# FPGABank3X.net
KiCad netlist of a schematic drawn in Altium Designer
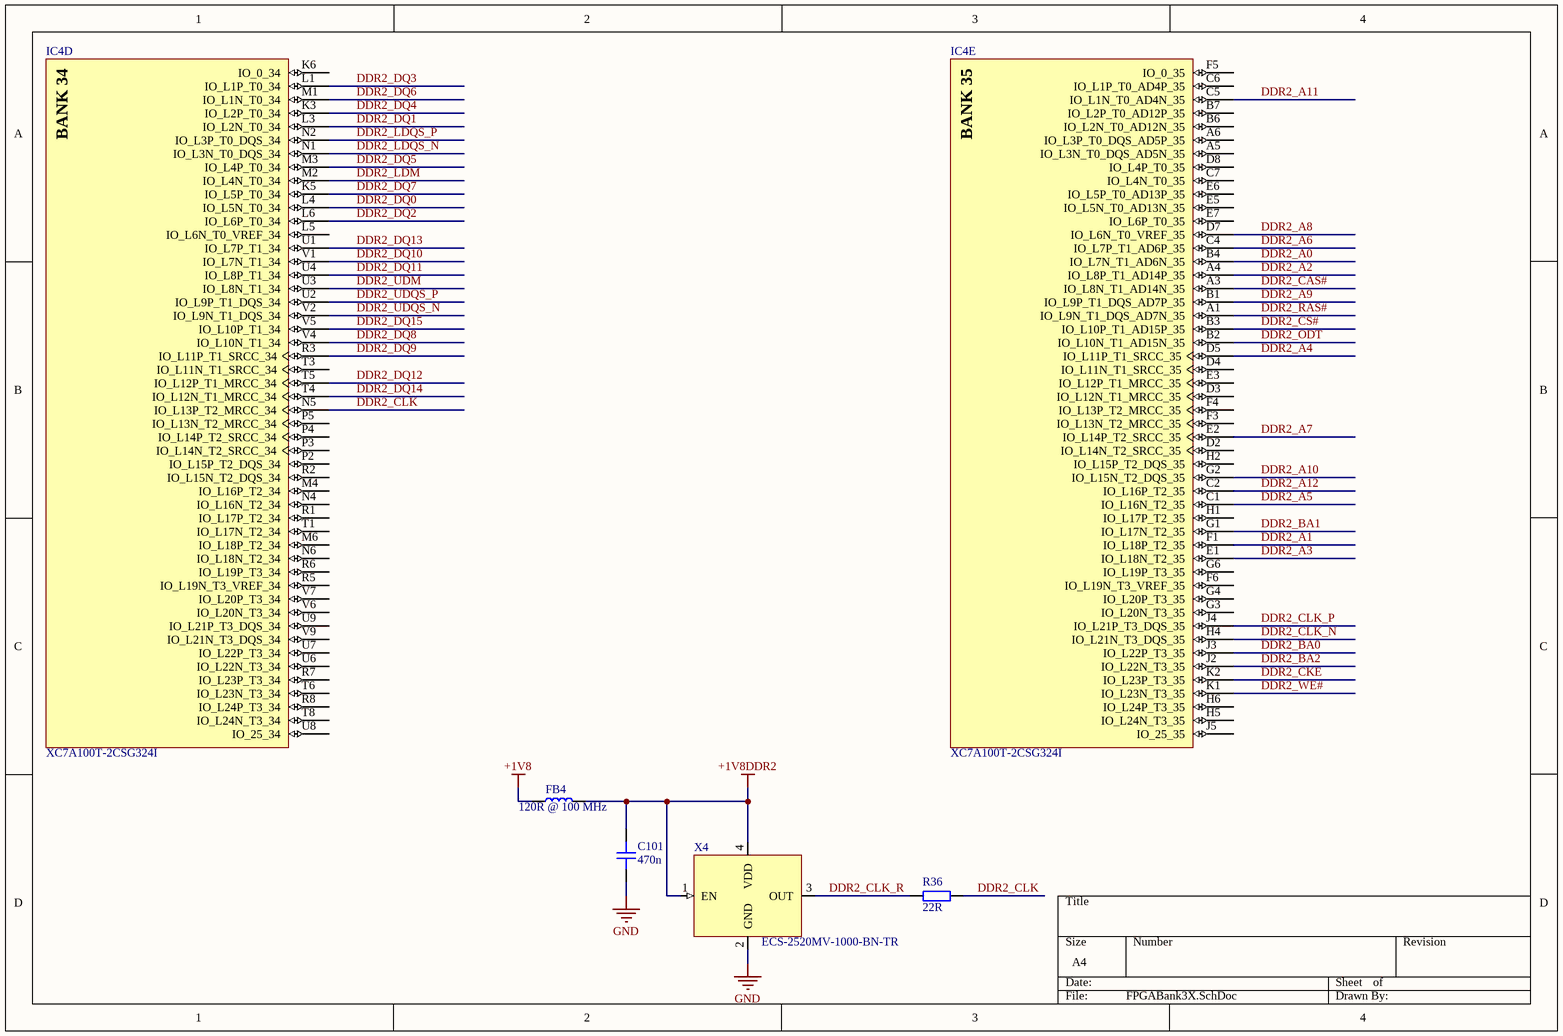
[diagram p0: FPGABank3X.SchDoc]

(export (version "E")
  (design (tool "Eeschema 10.0.6"))
  (components
    (comp (ref "C101")
      (value "470n")
      (footprint "CAP_0201")
      (description "Capacitor SMD 0201")
      (libsource (lib "Schematic-Lib-PhilsLab") (part "CAP_0201"))
    )
    (comp (ref "FB4")
      (value "120R @ 100 MHz")
      (footprint "Footprint-Lib-PhilsLab:IND_0201")
      (description "Inductor SMD 0201")
      (fields
        (field (name "MANUFACTURER_PART_NUMBER") "LQP03HQ56NH02D")
        (field (name "MOUSER PART NUMBER") "81-LQP03HQ56NH02D")
      )
      (libsource (lib "Schematic-Lib-PhilsLab") (part "IND_0201"))
    )
    (comp (ref "IC4")
      (value "XC7A100T-2CSG324I")
      (footprint "CSG324")
      (description "Artix-7 FPGA, 210 User I/Os, 0 GTP, 324-Ball BGA, Speed Grade 2, Industrial Grade, Pb-Free")
      (fields (field (name "GENERIC PART NUMBER") "XC7A100T") (field (name "MANUFACTURER") "Xilinx"))
      (libsource (lib "Schematic-Lib-PhilsLab") (part "XC7A100T-2CSG324I"))
    )
    (comp (ref "R36")
      (value "22R")
      (footprint "RES_0201")
      (description "Resistor SMD 0201")
      (libsource (lib "Schematic-Lib-PhilsLab") (part "RES_0201"))
    )
    (comp (ref "X4")
      (value "ECS-2520MV-1000-BN-TR")
      (footprint "XTAL_2520")
      (fields
        (field (name "MANUFACTURER") "ECS")
        (field (name "MANUFACTURER PART NUMBER") "ECS-2520MV-130-BN-TR")
      )
      (libsource (lib "Schematic-Lib-PhilsLab") (part "ECS-2520MV-130-BN-TR"))
    )
  )
  (nets
    (net (code "1") (name "+1V8") (class "Default")
      (node (ref "FB4") (pin "1") (pinfunction "1_1") (pintype "passive"))
    )
    (net (code "2") (name "+1V8DDR2") (class "Default")
      (node (ref "C101") (pin "2") (pinfunction "2_2") (pintype "passive"))
      (node (ref "FB4") (pin "2") (pinfunction "2_2") (pintype "passive"))
      (node (ref "X4") (pin "1") (pinfunction "EN_1") (pintype "input"))
      (node (ref "X4") (pin "4") (pinfunction "VDD_4") (pintype "power_in"))
    )
    (net (code "3") (name "/DDR2_A0") (class "Default")
      (node (ref "IC4") (pin "B4") (pinfunction "IO_L7N_T1_AD6N_35_B4") (pintype "bidirectional"))
    )
    (net (code "4") (name "/DDR2_A1") (class "Default")
      (node (ref "IC4") (pin "F1") (pinfunction "IO_L18P_T2_35_F1") (pintype "bidirectional"))
    )
    (net (code "5") (name "/DDR2_A2") (class "Default")
      (node (ref "IC4") (pin "A4") (pinfunction "IO_L8P_T1_AD14P_35_A4") (pintype "bidirectional"))
    )
    (net (code "6") (name "/DDR2_A3") (class "Default")
      (node (ref "IC4") (pin "E1") (pinfunction "IO_L18N_T2_35_E1") (pintype "bidirectional"))
    )
    (net (code "7") (name "/DDR2_A4") (class "Default")
      (node (ref "IC4") (pin "D5") (pinfunction "IO_L11P_T1_SRCC_35_D5") (pintype "bidirectional"))
    )
    (net (code "8") (name "/DDR2_A5") (class "Default")
      (node (ref "IC4") (pin "C1") (pinfunction "IO_L16N_T2_35_C1") (pintype "bidirectional"))
    )
    (net (code "9") (name "/DDR2_A6") (class "Default")
      (node (ref "IC4") (pin "C4") (pinfunction "IO_L7P_T1_AD6P_35_C4") (pintype "bidirectional"))
    )
    (net (code "10") (name "/DDR2_A7") (class "Default")
      (node (ref "IC4") (pin "E2") (pinfunction "IO_L14P_T2_SRCC_35_E2") (pintype "bidirectional"))
    )
    (net (code "11") (name "/DDR2_A8") (class "Default")
      (node (ref "IC4") (pin "D7") (pinfunction "IO_L6N_T0_VREF_35_D7") (pintype "bidirectional"))
    )
    (net (code "12") (name "/DDR2_A9") (class "Default")
      (node (ref "IC4") (pin "B1") (pinfunction "IO_L9P_T1_DQS_AD7P_35_B1") (pintype "bidirectional"))
    )
    (net (code "13") (name "/DDR2_A10") (class "Default")
      (node (ref "IC4") (pin "G2") (pinfunction "IO_L15N_T2_DQS_35_G2") (pintype "bidirectional"))
    )
    (net (code "14") (name "/DDR2_A11") (class "Default")
      (node (ref "IC4") (pin "C5") (pinfunction "IO_L1N_T0_AD4N_35_C5") (pintype "bidirectional"))
    )
    (net (code "15") (name "/DDR2_A12") (class "Default")
      (node (ref "IC4") (pin "C2") (pinfunction "IO_L16P_T2_35_C2") (pintype "bidirectional"))
    )
    (net (code "16") (name "/DDR2_BA0") (class "Default")
      (node (ref "IC4") (pin "J3") (pinfunction "IO_L22P_T3_35_J3") (pintype "bidirectional"))
    )
    (net (code "17") (name "/DDR2_BA1") (class "Default")
      (node (ref "IC4") (pin "G1") (pinfunction "IO_L17N_T2_35_G1") (pintype "bidirectional"))
    )
    (net (code "18") (name "/DDR2_BA2") (class "Default")
      (node (ref "IC4") (pin "J2") (pinfunction "IO_L22N_T3_35_J2") (pintype "bidirectional"))
    )
    (net (code "19") (name "/DDR2_CAS#") (class "Default")
      (node (ref "IC4") (pin "A3") (pinfunction "IO_L8N_T1_AD14N_35_A3") (pintype "bidirectional"))
    )
    (net (code "20") (name "/DDR2_CKE") (class "Default")
      (node (ref "IC4") (pin "K2") (pinfunction "IO_L23P_T3_35_K2") (pintype "bidirectional"))
    )
    (net (code "21") (name "/DDR2_CLK") (class "Default")
      (node (ref "IC4") (pin "N5") (pinfunction "IO_L13P_T2_MRCC_34_N5") (pintype "bidirectional"))
      (node (ref "R36") (pin "2") (pinfunction "2_2") (pintype "passive"))
    )
    (net (code "22") (name "/DDR2_CLK_N") (class "Default")
      (node (ref "IC4") (pin "H4") (pinfunction "IO_L21N_T3_DQS_35_H4") (pintype "bidirectional"))
    )
    (net (code "23") (name "/DDR2_CLK_P") (class "Default")
      (node (ref "IC4") (pin "J4") (pinfunction "IO_L21P_T3_DQS_35_J4") (pintype "bidirectional"))
    )
    (net (code "24") (name "/DDR2_CLK_R") (class "Default")
      (node (ref "R36") (pin "1") (pinfunction "1_1") (pintype "passive"))
      (node (ref "X4") (pin "3") (pinfunction "OUT_3") (pintype "passive"))
    )
    (net (code "25") (name "/DDR2_CS#") (class "Default")
      (node (ref "IC4") (pin "B3") (pinfunction "IO_L10P_T1_AD15P_35_B3") (pintype "bidirectional"))
    )
    (net (code "26") (name "/DDR2_DQ0") (class "Default")
      (node (ref "IC4") (pin "L4") (pinfunction "IO_L5N_T0_34_L4") (pintype "bidirectional"))
    )
    (net (code "27") (name "/DDR2_DQ1") (class "Default")
      (node (ref "IC4") (pin "L3") (pinfunction "IO_L2N_T0_34_L3") (pintype "bidirectional"))
    )
    (net (code "28") (name "/DDR2_DQ2") (class "Default")
      (node (ref "IC4") (pin "L6") (pinfunction "IO_L6P_T0_34_L6") (pintype "bidirectional"))
    )
    (net (code "29") (name "/DDR2_DQ3") (class "Default")
      (node (ref "IC4") (pin "L1") (pinfunction "IO_L1P_T0_34_L1") (pintype "bidirectional"))
    )
    (net (code "30") (name "/DDR2_DQ4") (class "Default")
      (node (ref "IC4") (pin "K3") (pinfunction "IO_L2P_T0_34_K3") (pintype "bidirectional"))
    )
    (net (code "31") (name "/DDR2_DQ5") (class "Default")
      (node (ref "IC4") (pin "M3") (pinfunction "IO_L4P_T0_34_M3") (pintype "bidirectional"))
    )
    (net (code "32") (name "/DDR2_DQ6") (class "Default")
      (node (ref "IC4") (pin "M1") (pinfunction "IO_L1N_T0_34_M1") (pintype "bidirectional"))
    )
    (net (code "33") (name "/DDR2_DQ7") (class "Default")
      (node (ref "IC4") (pin "K5") (pinfunction "IO_L5P_T0_34_K5") (pintype "bidirectional"))
    )
    (net (code "34") (name "/DDR2_DQ8") (class "Default")
      (node (ref "IC4") (pin "V4") (pinfunction "IO_L10N_T1_34_V4") (pintype "bidirectional"))
    )
    (net (code "35") (name "/DDR2_DQ9") (class "Default")
      (node (ref "IC4") (pin "R3") (pinfunction "IO_L11P_T1_SRCC_34_R3") (pintype "bidirectional"))
    )
    (net (code "36") (name "/DDR2_DQ10") (class "Default")
      (node (ref "IC4") (pin "V1") (pinfunction "IO_L7N_T1_34_V1") (pintype "bidirectional"))
    )
    (net (code "37") (name "/DDR2_DQ11") (class "Default")
      (node (ref "IC4") (pin "U4") (pinfunction "IO_L8P_T1_34_U4") (pintype "bidirectional"))
    )
    (net (code "38") (name "/DDR2_DQ12") (class "Default")
      (node (ref "IC4") (pin "T5") (pinfunction "IO_L12P_T1_MRCC_34_T5") (pintype "bidirectional"))
    )
    (net (code "39") (name "/DDR2_DQ13") (class "Default")
      (node (ref "IC4") (pin "U1") (pinfunction "IO_L7P_T1_34_U1") (pintype "bidirectional"))
    )
    (net (code "40") (name "/DDR2_DQ14") (class "Default")
      (node (ref "IC4") (pin "T4") (pinfunction "IO_L12N_T1_MRCC_34_T4") (pintype "bidirectional"))
    )
    (net (code "41") (name "/DDR2_DQ15") (class "Default")
      (node (ref "IC4") (pin "V5") (pinfunction "IO_L10P_T1_34_V5") (pintype "bidirectional"))
    )
    (net (code "42") (name "/DDR2_LDM") (class "Default")
      (node (ref "IC4") (pin "M2") (pinfunction "IO_L4N_T0_34_M2") (pintype "bidirectional"))
    )
    (net (code "43") (name "/DDR2_LDQS_N") (class "Default")
      (node (ref "IC4") (pin "N1") (pinfunction "IO_L3N_T0_DQS_34_N1") (pintype "bidirectional"))
    )
    (net (code "44") (name "/DDR2_LDQS_P") (class "Default")
      (node (ref "IC4") (pin "N2") (pinfunction "IO_L3P_T0_DQS_34_N2") (pintype "bidirectional"))
    )
    (net (code "45") (name "/DDR2_ODT") (class "Default")
      (node (ref "IC4") (pin "B2") (pinfunction "IO_L10N_T1_AD15N_35_B2") (pintype "bidirectional"))
    )
    (net (code "46") (name "/DDR2_RAS#") (class "Default")
      (node (ref "IC4") (pin "A1") (pinfunction "IO_L9N_T1_DQS_AD7N_35_A1") (pintype "bidirectional"))
    )
    (net (code "47") (name "/DDR2_UDM") (class "Default")
      (node (ref "IC4") (pin "U3") (pinfunction "IO_L8N_T1_34_U3") (pintype "bidirectional"))
    )
    (net (code "48") (name "/DDR2_UDQS_N") (class "Default")
      (node (ref "IC4") (pin "V2") (pinfunction "IO_L9N_T1_DQS_34_V2") (pintype "bidirectional"))
    )
    (net (code "49") (name "/DDR2_UDQS_P") (class "Default")
      (node (ref "IC4") (pin "U2") (pinfunction "IO_L9P_T1_DQS_34_U2") (pintype "bidirectional"))
    )
    (net (code "50") (name "/DDR2_WE#") (class "Default")
      (node (ref "IC4") (pin "K1") (pinfunction "IO_L23N_T3_35_K1") (pintype "bidirectional"))
    )
    (net (code "51") (name "GND") (class "Default")
      (node (ref "C101") (pin "1") (pinfunction "1_1") (pintype "passive"))
      (node (ref "X4") (pin "2") (pinfunction "GND_2") (pintype "power_in"))
    )
    (net (code "52") (name "unconnected-(IC4D-IO_0_34-PadK6)") (class "Default")
      (node (ref "IC4") (pin "K6") (pinfunction "IO_0_34_K6") (pintype "bidirectional"))
    )
    (net (code "53") (name "unconnected-(IC4D-IO_25_34-PadU8)") (class "Default")
      (node (ref "IC4") (pin "U8") (pinfunction "IO_25_34_U8") (pintype "bidirectional"))
    )
    (net (code "54") (name "unconnected-(IC4D-IO_L6N_T0_VREF_34-PadL5)") (class "Default")
      (node (ref "IC4") (pin "L5") (pinfunction "IO_L6N_T0_VREF_34_L5") (pintype "bidirectional"))
    )
    (net (code "55") (name "unconnected-(IC4D-IO_L11N_T1_SRCC_34-PadT3)") (class "Default")
      (node (ref "IC4") (pin "T3") (pinfunction "IO_L11N_T1_SRCC_34_T3") (pintype "bidirectional"))
    )
    (net (code "56") (name "unconnected-(IC4D-IO_L13N_T2_MRCC_34-PadP5)") (class "Default")
      (node (ref "IC4") (pin "P5") (pinfunction "IO_L13N_T2_MRCC_34_P5") (pintype "bidirectional"))
    )
    (net (code "57") (name "unconnected-(IC4D-IO_L14N_T2_SRCC_34-PadP3)") (class "Default")
      (node (ref "IC4") (pin "P3") (pinfunction "IO_L14N_T2_SRCC_34_P3") (pintype "bidirectional"))
    )
    (net (code "58") (name "unconnected-(IC4D-IO_L14P_T2_SRCC_34-PadP4)") (class "Default")
      (node (ref "IC4") (pin "P4") (pinfunction "IO_L14P_T2_SRCC_34_P4") (pintype "bidirectional"))
    )
    (net (code "59") (name "unconnected-(IC4D-IO_L15N_T2_DQS_34-PadR2)") (class "Default")
      (node (ref "IC4") (pin "R2") (pinfunction "IO_L15N_T2_DQS_34_R2") (pintype "bidirectional"))
    )
    (net (code "60") (name "unconnected-(IC4D-IO_L15P_T2_DQS_34-PadP2)") (class "Default")
      (node (ref "IC4") (pin "P2") (pinfunction "IO_L15P_T2_DQS_34_P2") (pintype "bidirectional"))
    )
    (net (code "61") (name "unconnected-(IC4D-IO_L16N_T2_34-PadN4)") (class "Default")
      (node (ref "IC4") (pin "N4") (pinfunction "IO_L16N_T2_34_N4") (pintype "bidirectional"))
    )
    (net (code "62") (name "unconnected-(IC4D-IO_L16P_T2_34-PadM4)") (class "Default")
      (node (ref "IC4") (pin "M4") (pinfunction "IO_L16P_T2_34_M4") (pintype "bidirectional"))
    )
    (net (code "63") (name "unconnected-(IC4D-IO_L17N_T2_34-PadT1)") (class "Default")
      (node (ref "IC4") (pin "T1") (pinfunction "IO_L17N_T2_34_T1") (pintype "bidirectional"))
    )
    (net (code "64") (name "unconnected-(IC4D-IO_L17P_T2_34-PadR1)") (class "Default")
      (node (ref "IC4") (pin "R1") (pinfunction "IO_L17P_T2_34_R1") (pintype "bidirectional"))
    )
    (net (code "65") (name "unconnected-(IC4D-IO_L18N_T2_34-PadN6)") (class "Default")
      (node (ref "IC4") (pin "N6") (pinfunction "IO_L18N_T2_34_N6") (pintype "bidirectional"))
    )
    (net (code "66") (name "unconnected-(IC4D-IO_L18P_T2_34-PadM6)") (class "Default")
      (node (ref "IC4") (pin "M6") (pinfunction "IO_L18P_T2_34_M6") (pintype "bidirectional"))
    )
    (net (code "67") (name "unconnected-(IC4D-IO_L19N_T3_VREF_34-PadR5)") (class "Default")
      (node (ref "IC4") (pin "R5") (pinfunction "IO_L19N_T3_VREF_34_R5") (pintype "bidirectional"))
    )
    (net (code "68") (name "unconnected-(IC4D-IO_L19P_T3_34-PadR6)") (class "Default")
      (node (ref "IC4") (pin "R6") (pinfunction "IO_L19P_T3_34_R6") (pintype "bidirectional"))
    )
    (net (code "69") (name "unconnected-(IC4D-IO_L20N_T3_34-PadV6)") (class "Default")
      (node (ref "IC4") (pin "V6") (pinfunction "IO_L20N_T3_34_V6") (pintype "bidirectional"))
    )
    (net (code "70") (name "unconnected-(IC4D-IO_L20P_T3_34-PadV7)") (class "Default")
      (node (ref "IC4") (pin "V7") (pinfunction "IO_L20P_T3_34_V7") (pintype "bidirectional"))
    )
    (net (code "71") (name "unconnected-(IC4D-IO_L21N_T3_DQS_34-PadV9)") (class "Default")
      (node (ref "IC4") (pin "V9") (pinfunction "IO_L21N_T3_DQS_34_V9") (pintype "bidirectional"))
    )
    (net (code "72") (name "unconnected-(IC4D-IO_L21P_T3_DQS_34-PadU9)") (class "Default")
      (node (ref "IC4") (pin "U9") (pinfunction "IO_L21P_T3_DQS_34_U9") (pintype "bidirectional"))
    )
    (net (code "73") (name "unconnected-(IC4D-IO_L22N_T3_34-PadU6)") (class "Default")
      (node (ref "IC4") (pin "U6") (pinfunction "IO_L22N_T3_34_U6") (pintype "bidirectional"))
    )
    (net (code "74") (name "unconnected-(IC4D-IO_L22P_T3_34-PadU7)") (class "Default")
      (node (ref "IC4") (pin "U7") (pinfunction "IO_L22P_T3_34_U7") (pintype "bidirectional"))
    )
    (net (code "75") (name "unconnected-(IC4D-IO_L23N_T3_34-PadT6)") (class "Default")
      (node (ref "IC4") (pin "T6") (pinfunction "IO_L23N_T3_34_T6") (pintype "bidirectional"))
    )
    (net (code "76") (name "unconnected-(IC4D-IO_L23P_T3_34-PadR7)") (class "Default")
      (node (ref "IC4") (pin "R7") (pinfunction "IO_L23P_T3_34_R7") (pintype "bidirectional"))
    )
    (net (code "77") (name "unconnected-(IC4D-IO_L24N_T3_34-PadT8)") (class "Default")
      (node (ref "IC4") (pin "T8") (pinfunction "IO_L24N_T3_34_T8") (pintype "bidirectional"))
    )
    (net (code "78") (name "unconnected-(IC4D-IO_L24P_T3_34-PadR8)") (class "Default")
      (node (ref "IC4") (pin "R8") (pinfunction "IO_L24P_T3_34_R8") (pintype "bidirectional"))
    )
    (net (code "79") (name "unconnected-(IC4E-IO_0_35-PadF5)") (class "Default")
      (node (ref "IC4") (pin "F5") (pinfunction "IO_0_35_F5") (pintype "bidirectional"))
    )
    (net (code "80") (name "unconnected-(IC4E-IO_25_35-PadJ5)") (class "Default")
      (node (ref "IC4") (pin "J5") (pinfunction "IO_25_35_J5") (pintype "bidirectional"))
    )
    (net (code "81") (name "unconnected-(IC4E-IO_L1P_T0_AD4P_35-PadC6)") (class "Default")
      (node (ref "IC4") (pin "C6") (pinfunction "IO_L1P_T0_AD4P_35_C6") (pintype "bidirectional"))
    )
    (net (code "82") (name "unconnected-(IC4E-IO_L2N_T0_AD12N_35-PadB6)") (class "Default")
      (node (ref "IC4") (pin "B6") (pinfunction "IO_L2N_T0_AD12N_35_B6") (pintype "bidirectional"))
    )
    (net (code "83") (name "unconnected-(IC4E-IO_L2P_T0_AD12P_35-PadB7)") (class "Default")
      (node (ref "IC4") (pin "B7") (pinfunction "IO_L2P_T0_AD12P_35_B7") (pintype "bidirectional"))
    )
    (net (code "84") (name "unconnected-(IC4E-IO_L3N_T0_DQS_AD5N_35-PadA5)") (class "Default")
      (node (ref "IC4") (pin "A5") (pinfunction "IO_L3N_T0_DQS_AD5N_35_A5") (pintype "bidirectional"))
    )
    (net (code "85") (name "unconnected-(IC4E-IO_L3P_T0_DQS_AD5P_35-PadA6)") (class "Default")
      (node (ref "IC4") (pin "A6") (pinfunction "IO_L3P_T0_DQS_AD5P_35_A6") (pintype "bidirectional"))
    )
    (net (code "86") (name "unconnected-(IC4E-IO_L4N_T0_35-PadC7)") (class "Default")
      (node (ref "IC4") (pin "C7") (pinfunction "IO_L4N_T0_35_C7") (pintype "bidirectional"))
    )
    (net (code "87") (name "unconnected-(IC4E-IO_L4P_T0_35-PadD8)") (class "Default")
      (node (ref "IC4") (pin "D8") (pinfunction "IO_L4P_T0_35_D8") (pintype "bidirectional"))
    )
    (net (code "88") (name "unconnected-(IC4E-IO_L5N_T0_AD13N_35-PadE5)") (class "Default")
      (node (ref "IC4") (pin "E5") (pinfunction "IO_L5N_T0_AD13N_35_E5") (pintype "bidirectional"))
    )
    (net (code "89") (name "unconnected-(IC4E-IO_L5P_T0_AD13P_35-PadE6)") (class "Default")
      (node (ref "IC4") (pin "E6") (pinfunction "IO_L5P_T0_AD13P_35_E6") (pintype "bidirectional"))
    )
    (net (code "90") (name "unconnected-(IC4E-IO_L6P_T0_35-PadE7)") (class "Default")
      (node (ref "IC4") (pin "E7") (pinfunction "IO_L6P_T0_35_E7") (pintype "bidirectional"))
    )
    (net (code "91") (name "unconnected-(IC4E-IO_L11N_T1_SRCC_35-PadD4)") (class "Default")
      (node (ref "IC4") (pin "D4") (pinfunction "IO_L11N_T1_SRCC_35_D4") (pintype "bidirectional"))
    )
    (net (code "92") (name "unconnected-(IC4E-IO_L12N_T1_MRCC_35-PadD3)") (class "Default")
      (node (ref "IC4") (pin "D3") (pinfunction "IO_L12N_T1_MRCC_35_D3") (pintype "bidirectional"))
    )
    (net (code "93") (name "unconnected-(IC4E-IO_L12P_T1_MRCC_35-PadE3)") (class "Default")
      (node (ref "IC4") (pin "E3") (pinfunction "IO_L12P_T1_MRCC_35_E3") (pintype "bidirectional"))
    )
    (net (code "94") (name "unconnected-(IC4E-IO_L13N_T2_MRCC_35-PadF3)") (class "Default")
      (node (ref "IC4") (pin "F3") (pinfunction "IO_L13N_T2_MRCC_35_F3") (pintype "bidirectional"))
    )
    (net (code "95") (name "unconnected-(IC4E-IO_L13P_T2_MRCC_35-PadF4)") (class "Default")
      (node (ref "IC4") (pin "F4") (pinfunction "IO_L13P_T2_MRCC_35_F4") (pintype "bidirectional"))
    )
    (net (code "96") (name "unconnected-(IC4E-IO_L14N_T2_SRCC_35-PadD2)") (class "Default")
      (node (ref "IC4") (pin "D2") (pinfunction "IO_L14N_T2_SRCC_35_D2") (pintype "bidirectional"))
    )
    (net (code "97") (name "unconnected-(IC4E-IO_L15P_T2_DQS_35-PadH2)") (class "Default")
      (node (ref "IC4") (pin "H2") (pinfunction "IO_L15P_T2_DQS_35_H2") (pintype "bidirectional"))
    )
    (net (code "98") (name "unconnected-(IC4E-IO_L17P_T2_35-PadH1)") (class "Default")
      (node (ref "IC4") (pin "H1") (pinfunction "IO_L17P_T2_35_H1") (pintype "bidirectional"))
    )
    (net (code "99") (name "unconnected-(IC4E-IO_L19N_T3_VREF_35-PadF6)") (class "Default")
      (node (ref "IC4") (pin "F6") (pinfunction "IO_L19N_T3_VREF_35_F6") (pintype "bidirectional"))
    )
    (net (code "100") (name "unconnected-(IC4E-IO_L19P_T3_35-PadG6)") (class "Default")
      (node (ref "IC4") (pin "G6") (pinfunction "IO_L19P_T3_35_G6") (pintype "bidirectional"))
    )
    (net (code "101") (name "unconnected-(IC4E-IO_L20N_T3_35-PadG3)") (class "Default")
      (node (ref "IC4") (pin "G3") (pinfunction "IO_L20N_T3_35_G3") (pintype "bidirectional"))
    )
    (net (code "102") (name "unconnected-(IC4E-IO_L20P_T3_35-PadG4)") (class "Default")
      (node (ref "IC4") (pin "G4") (pinfunction "IO_L20P_T3_35_G4") (pintype "bidirectional"))
    )
    (net (code "103") (name "unconnected-(IC4E-IO_L24N_T3_35-PadH5)") (class "Default")
      (node (ref "IC4") (pin "H5") (pinfunction "IO_L24N_T3_35_H5") (pintype "bidirectional"))
    )
    (net (code "104") (name "unconnected-(IC4E-IO_L24P_T3_35-PadH6)") (class "Default")
      (node (ref "IC4") (pin "H6") (pinfunction "IO_L24P_T3_35_H6") (pintype "bidirectional"))
    )
  )
)
